# trinket-mcp23017.net
KiCad netlist of a schematic drawn in EAGLE
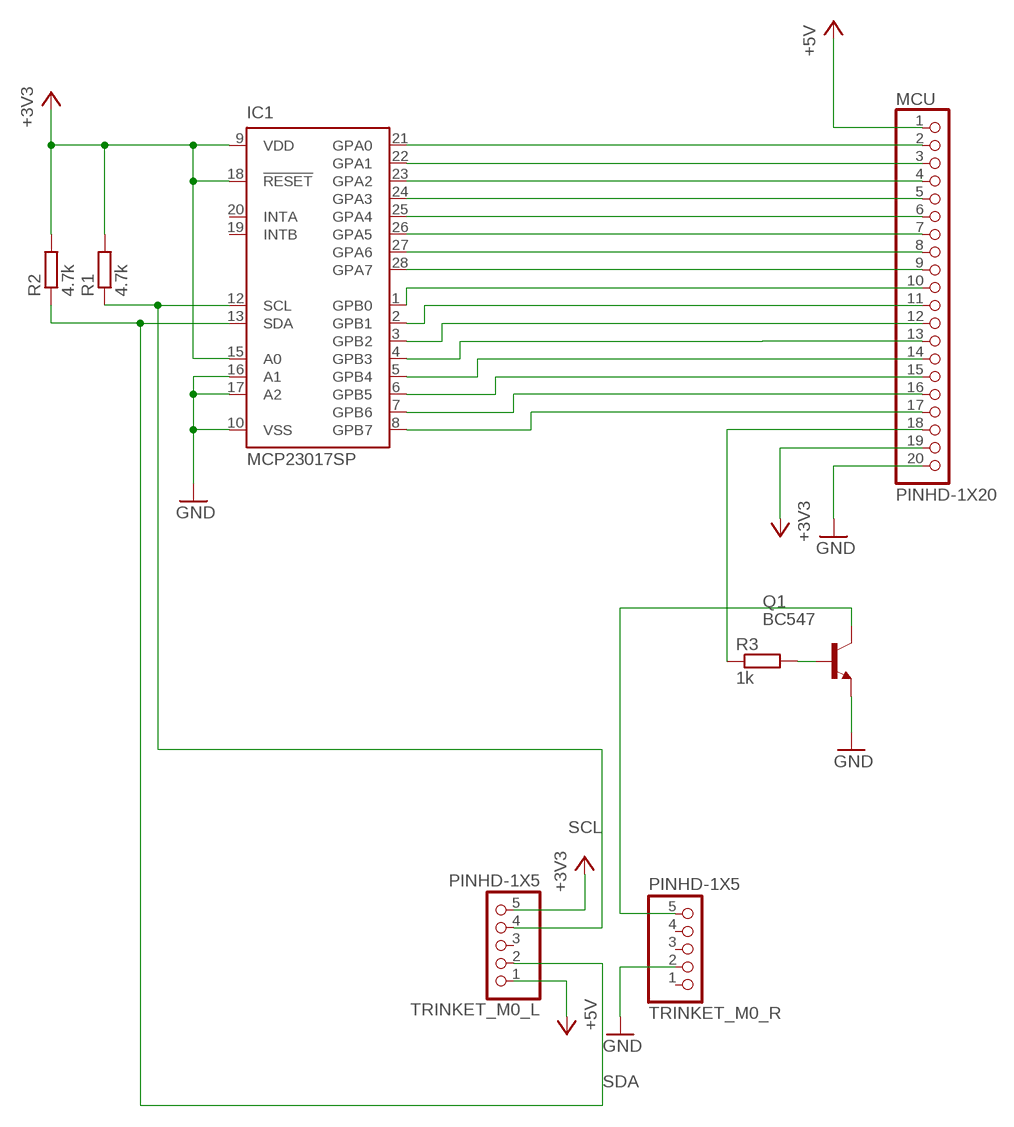
[diagram p0: schematic, sheet 1]

(export (version "E")
  (design (tool "Eeschema 10.0.6"))
  (components
    (comp (ref "IC1")
      (value "MCP23017SP")
      (footprint "eagle-import:DIL28-3")
      (fields (field (name "MF") "MICROCHIP") (field (name "MPN") "MCP23017-E/SP"))
      (libsource (lib "eagle-import") (part "MCP23017SP"))
    )
    (comp (ref "MCU")
      (value "PINHD-1X20")
      (footprint "eagle-import:1X20")
      (libsource (lib "eagle-import") (part "PINHD-1X20"))
    )
    (comp (ref "Q1")
      (value "BC547")
      (footprint "eagle-import:TO92")
      (libsource (lib "eagle-import") (part "BC547"))
    )
    (comp (ref "R1")
      (value "4.7k")
      (footprint "eagle-import:0207_10")
      (libsource (lib "eagle-import") (part "R-EU_0207/10"))
    )
    (comp (ref "R2")
      (value "4.7k")
      (footprint "eagle-import:0207_10")
      (libsource (lib "eagle-import") (part "R-EU_0207/10"))
    )
    (comp (ref "R3")
      (value "1k")
      (footprint "eagle-import:0207_10")
      (libsource (lib "eagle-import") (part "R-EU_0207/10"))
    )
    (comp (ref "TRINKET_M0_L")
      (value "PINHD-1X5")
      (footprint "eagle-import:1X05")
      (libsource (lib "eagle-import") (part "PINHD-1X5"))
    )
    (comp (ref "TRINKET_M0_R")
      (value "PINHD-1X5")
      (footprint "eagle-import:1X05")
      (libsource (lib "eagle-import") (part "PINHD-1X5"))
    )
  )
  (nets
    (net (code "1") (name "+3V3") (class "Default")
      (node (ref "IC1") (pin "15") (pinfunction "A0_15") (pintype "input"))
      (node (ref "IC1") (pin "18") (pinfunction "~{RESET}_18") (pintype "input"))
      (node (ref "IC1") (pin "9") (pinfunction "VDD_9") (pintype "power_in"))
      (node (ref "MCU") (pin "19") (pinfunction "19_19") (pintype "passive"))
      (node (ref "R1") (pin "2") (pinfunction "2_2") (pintype "passive"))
      (node (ref "R2") (pin "2") (pinfunction "2_2") (pintype "passive"))
      (node (ref "TRINKET_M0_L") (pin "5") (pinfunction "5_5") (pintype "passive"))
    )
    (net (code "2") (name "+5V") (class "Default")
      (node (ref "MCU") (pin "1") (pinfunction "1_1") (pintype "passive"))
      (node (ref "TRINKET_M0_L") (pin "1") (pinfunction "1_1") (pintype "passive"))
    )
    (net (code "3") (name "/SCL") (class "Default")
      (node (ref "IC1") (pin "12") (pinfunction "SCL_12") (pintype "input"))
      (node (ref "R1") (pin "1") (pinfunction "1_1") (pintype "passive"))
      (node (ref "TRINKET_M0_L") (pin "4") (pinfunction "4_4") (pintype "passive"))
    )
    (net (code "4") (name "/SDA") (class "Default")
      (node (ref "IC1") (pin "13") (pinfunction "SDA_13") (pintype "bidirectional"))
      (node (ref "R2") (pin "1") (pinfunction "1_1") (pintype "passive"))
      (node (ref "TRINKET_M0_L") (pin "2") (pinfunction "2_2") (pintype "passive"))
    )
    (net (code "5") (name "GND") (class "Default")
      (node (ref "IC1") (pin "10") (pinfunction "VSS_10") (pintype "power_in"))
      (node (ref "IC1") (pin "16") (pinfunction "A1_16") (pintype "input"))
      (node (ref "IC1") (pin "17") (pinfunction "A2_17") (pintype "input"))
      (node (ref "MCU") (pin "20") (pinfunction "20_20") (pintype "passive"))
      (node (ref "Q1") (pin "1") (pinfunction "E_1") (pintype "passive"))
      (node (ref "TRINKET_M0_R") (pin "2") (pinfunction "2_2") (pintype "passive"))
    )
    (net (code "6") (name "Net-(IC1-GPA0)") (class "Default")
      (node (ref "IC1") (pin "21") (pinfunction "GPA0_21") (pintype "bidirectional"))
      (node (ref "MCU") (pin "2") (pinfunction "2_2") (pintype "passive"))
    )
    (net (code "7") (name "Net-(IC1-GPA1)") (class "Default")
      (node (ref "IC1") (pin "22") (pinfunction "GPA1_22") (pintype "bidirectional"))
      (node (ref "MCU") (pin "3") (pinfunction "3_3") (pintype "passive"))
    )
    (net (code "8") (name "Net-(IC1-GPA2)") (class "Default")
      (node (ref "IC1") (pin "23") (pinfunction "GPA2_23") (pintype "bidirectional"))
      (node (ref "MCU") (pin "4") (pinfunction "4_4") (pintype "passive"))
    )
    (net (code "9") (name "Net-(IC1-GPA3)") (class "Default")
      (node (ref "IC1") (pin "24") (pinfunction "GPA3_24") (pintype "bidirectional"))
      (node (ref "MCU") (pin "5") (pinfunction "5_5") (pintype "passive"))
    )
    (net (code "10") (name "Net-(IC1-GPA4)") (class "Default")
      (node (ref "IC1") (pin "25") (pinfunction "GPA4_25") (pintype "bidirectional"))
      (node (ref "MCU") (pin "6") (pinfunction "6_6") (pintype "passive"))
    )
    (net (code "11") (name "Net-(IC1-GPA5)") (class "Default")
      (node (ref "IC1") (pin "26") (pinfunction "GPA5_26") (pintype "bidirectional"))
      (node (ref "MCU") (pin "7") (pinfunction "7_7") (pintype "passive"))
    )
    (net (code "12") (name "Net-(IC1-GPA6)") (class "Default")
      (node (ref "IC1") (pin "27") (pinfunction "GPA6_27") (pintype "bidirectional"))
      (node (ref "MCU") (pin "8") (pinfunction "8_8") (pintype "passive"))
    )
    (net (code "13") (name "Net-(IC1-GPA7)") (class "Default")
      (node (ref "IC1") (pin "28") (pinfunction "GPA7_28") (pintype "bidirectional"))
      (node (ref "MCU") (pin "9") (pinfunction "9_9") (pintype "passive"))
    )
    (net (code "14") (name "Net-(IC1-GPB0)") (class "Default")
      (node (ref "IC1") (pin "1") (pinfunction "GPB0_1") (pintype "bidirectional"))
      (node (ref "MCU") (pin "10") (pinfunction "10_10") (pintype "passive"))
    )
    (net (code "15") (name "Net-(IC1-GPB1)") (class "Default")
      (node (ref "IC1") (pin "2") (pinfunction "GPB1_2") (pintype "bidirectional"))
      (node (ref "MCU") (pin "11") (pinfunction "11_11") (pintype "passive"))
    )
    (net (code "16") (name "Net-(IC1-GPB2)") (class "Default")
      (node (ref "IC1") (pin "3") (pinfunction "GPB2_3") (pintype "bidirectional"))
      (node (ref "MCU") (pin "12") (pinfunction "12_12") (pintype "passive"))
    )
    (net (code "17") (name "Net-(IC1-GPB3)") (class "Default")
      (node (ref "IC1") (pin "4") (pinfunction "GPB3_4") (pintype "bidirectional"))
      (node (ref "MCU") (pin "13") (pinfunction "13_13") (pintype "passive"))
    )
    (net (code "18") (name "Net-(IC1-GPB4)") (class "Default")
      (node (ref "IC1") (pin "5") (pinfunction "GPB4_5") (pintype "bidirectional"))
      (node (ref "MCU") (pin "14") (pinfunction "14_14") (pintype "passive"))
    )
    (net (code "19") (name "Net-(IC1-GPB5)") (class "Default")
      (node (ref "IC1") (pin "6") (pinfunction "GPB5_6") (pintype "bidirectional"))
      (node (ref "MCU") (pin "15") (pinfunction "15_15") (pintype "passive"))
    )
    (net (code "20") (name "Net-(IC1-GPB6)") (class "Default")
      (node (ref "IC1") (pin "7") (pinfunction "GPB6_7") (pintype "bidirectional"))
      (node (ref "MCU") (pin "16") (pinfunction "16_16") (pintype "passive"))
    )
    (net (code "21") (name "Net-(IC1-GPB7)") (class "Default")
      (node (ref "IC1") (pin "8") (pinfunction "GPB7_8") (pintype "bidirectional"))
      (node (ref "MCU") (pin "17") (pinfunction "17_17") (pintype "passive"))
    )
    (net (code "22") (name "Net-(MCU-Pad18)") (class "Default")
      (node (ref "MCU") (pin "18") (pinfunction "18_18") (pintype "passive"))
      (node (ref "R3") (pin "1") (pinfunction "1_1") (pintype "passive"))
    )
    (net (code "23") (name "Net-(Q1-B)") (class "Default")
      (node (ref "Q1") (pin "2") (pinfunction "B_2") (pintype "passive"))
      (node (ref "R3") (pin "2") (pinfunction "2_2") (pintype "passive"))
    )
    (net (code "24") (name "Net-(Q1-C)") (class "Default")
      (node (ref "Q1") (pin "3") (pinfunction "C_3") (pintype "passive"))
      (node (ref "TRINKET_M0_R") (pin "5") (pinfunction "5_5") (pintype "passive"))
    )
    (net (code "25") (name "unconnected-(IC1-INTA-Pad20)") (class "Default")
      (node (ref "IC1") (pin "20") (pinfunction "INTA_20") (pintype "output"))
    )
    (net (code "26") (name "unconnected-(IC1-INTB-Pad19)") (class "Default")
      (node (ref "IC1") (pin "19") (pinfunction "INTB_19") (pintype "output"))
    )
    (net (code "27") (name "unconnected-(TRINKET_M0_L-Pad3)") (class "Default")
      (node (ref "TRINKET_M0_L") (pin "3") (pinfunction "3_3") (pintype "passive"))
    )
    (net (code "28") (name "unconnected-(TRINKET_M0_R-Pad1)") (class "Default")
      (node (ref "TRINKET_M0_R") (pin "1") (pinfunction "1_1") (pintype "passive"))
    )
    (net (code "29") (name "unconnected-(TRINKET_M0_R-Pad3)") (class "Default")
      (node (ref "TRINKET_M0_R") (pin "3") (pinfunction "3_3") (pintype "passive"))
    )
    (net (code "30") (name "unconnected-(TRINKET_M0_R-Pad4)") (class "Default")
      (node (ref "TRINKET_M0_R") (pin "4") (pinfunction "4_4") (pintype "passive"))
    )
  )
)
